# MY_DEMO_12864.net
KiCad netlist of a schematic drawn in Altium Designer
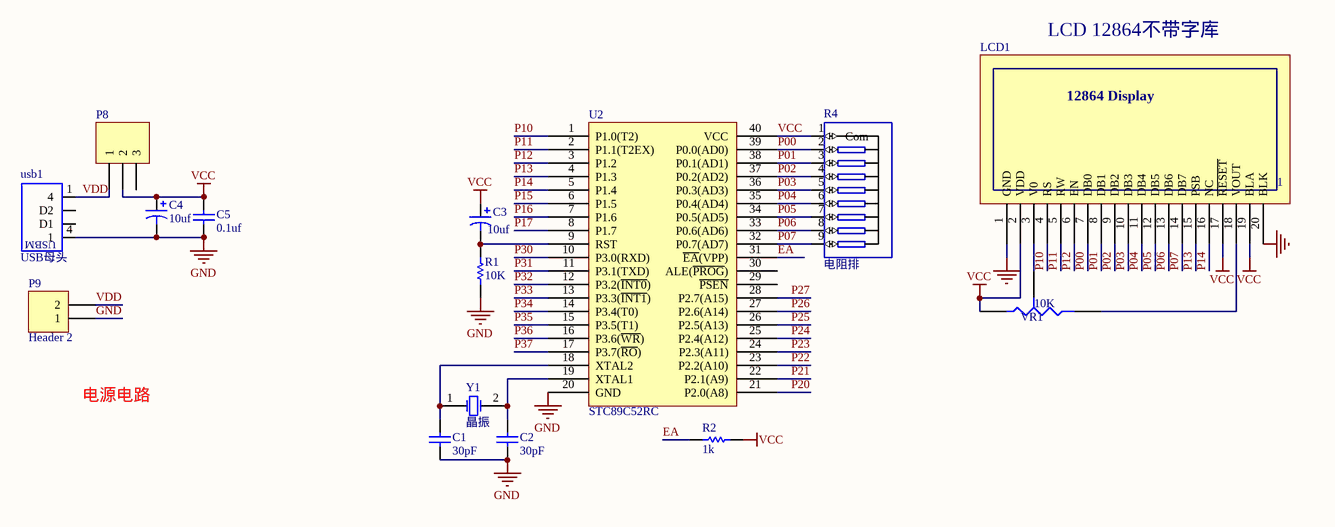
[diagram p0: MY_DEMO_12864.SchDoc]

(export (version "E")
  (design (tool "Eeschema 10.0.6"))
  (components
    (comp (ref "C1")
      (value "30pF")
      (footprint "RAD-0.1")
      (description "Capacitor")
      (fields (field (name "Comment") "瓷片电容") (field (name "PUBLISHER") "Altium Limited"))
      (libsource (lib "Miscellaneous Devices") (part "Cap"))
    )
    (comp (ref "C2")
      (value "30pF")
      (footprint "RAD-0.1")
      (description "Capacitor")
      (fields (field (name "Comment") "瓷片电容") (field (name "PUBLISHER") "Altium Limited"))
      (libsource (lib "Miscellaneous Devices") (part "Cap"))
    )
    (comp (ref "C3")
      (value "10uf")
      (footprint "10UF")
      (description "Polarized Capacitor (Radial)")
      (fields (field (name "Comment") "电解电容") (field (name "PUBLISHER") "Altium Limited"))
      (libsource (lib "Miscellaneous Devices") (part "Cap Pol1"))
    )
    (comp (ref "C4")
      (value "10uf")
      (footprint "10UF")
      (description "Polarized Capacitor (Radial)")
      (fields (field (name "Comment") "点解电容") (field (name "PUBLISHER") "Altium Limited"))
      (libsource (lib "Miscellaneous Devices") (part "Cap Pol1"))
    )
    (comp (ref "C5")
      (value "0.1uf")
      (footprint "CB1")
      (description "Capacitor")
      (fields (field (name "Comment") "瓷片电容") (field (name "PUBLISHER") "Altium Limited"))
      (libsource (lib "Miscellaneous Devices") (part "Cap"))
    )
    (comp (ref "LCD1") (value "1") (footprint "12864") (libsource (lib "*") (part "LCD12864-CK")))
    (comp (ref "P8")
      (value "Header 3")
      (footprint "HDR1X3")
      (description "Header, 3-Pin")
      (fields (field (name "PUBLISHER") "Altium Limited"))
      (libsource (lib "Miscellaneous Connectors") (part "Header 3"))
    )
    (comp (ref "P9")
      (value "Header 2")
      (footprint "HDR1X2")
      (description "Header, 2-Pin")
      (fields (field (name "PUBLISHER") "Altium Limited"))
      (libsource (lib "Miscellaneous Connectors") (part "Header 2"))
    )
    (comp (ref "R1")
      (value "10K")
      (footprint "电阻0.7-1.6")
      (description "Resistor")
      (fields (field (name "Comment") "电阻") (field (name "PUBLISHER") "Altium Limited"))
      (libsource (lib "Miscellaneous Devices") (part "Res1"))
    )
    (comp (ref "R2")
      (value "1k")
      (footprint "电阻0.7-1.6")
      (description "Resistor")
      (fields (field (name "Comment") "电阻") (field (name "PUBLISHER") "Altium Limited"))
      (libsource (lib "Miscellaneous Devices") (part "Res1"))
    )
    (comp (ref "R4") (value "电阻排") (footprint "插槽P9") (libsource (lib "电阻") (part "RES10")))
    (comp (ref "U2") (value "STC89C52RC") (footprint "DIP-40W") (libsource (lib "51单片机") (part "89C52")))
    (comp (ref "usb1") (value "USB母头") (footprint "A母USB") (libsource (lib "常用2") (part "USB")))
    (comp (ref "VR1")
      (value "12864")
      (footprint "RW")
      (fields (field (name "ALTIUM_UNNAMED_1") "10K"))
      (libsource (lib "*") (part "RES-TAP"))
    )
    (comp (ref "Y1")
      (value "晶振")
      (footprint "XTAL")
      (description "Crystal Oscillator")
      (fields (field (name "PUBLISHER") "Altium Limited"))
      (libsource (lib "Miscellaneous Devices") (part "XTAL"))
    )
  )
  (nets
    (net (code "1") (name "/EA") (class "Default")
      (node (ref "R2") (pin "2") (pinfunction "2_2") (pintype "passive"))
      (node (ref "U2") (pin "31") (pinfunction "~{EA}(VPP)_31") (pintype "passive"))
    )
    (net (code "3") (name "/P00") (class "Default")
      (node (ref "LCD1") (pin "7") (pinfunction "DB0_7") (pintype "passive"))
      (node (ref "R4") (pin "2") (pinfunction "2_2") (pintype "bidirectional"))
      (node (ref "U2") (pin "39") (pinfunction "P0.0(AD0)_39") (pintype "passive"))
    )
    (net (code "4") (name "/P01") (class "Default")
      (node (ref "LCD1") (pin "8") (pinfunction "DB1_8") (pintype "passive"))
      (node (ref "R4") (pin "3") (pinfunction "3_3") (pintype "bidirectional"))
      (node (ref "U2") (pin "38") (pinfunction "P0.1(AD1)_38") (pintype "passive"))
    )
    (net (code "5") (name "/P02") (class "Default")
      (node (ref "LCD1") (pin "9") (pinfunction "DB2_9") (pintype "passive"))
      (node (ref "R4") (pin "4") (pinfunction "4_4") (pintype "bidirectional"))
      (node (ref "U2") (pin "37") (pinfunction "P0.2(AD2)_37") (pintype "passive"))
    )
    (net (code "6") (name "/P03") (class "Default")
      (node (ref "LCD1") (pin "10") (pinfunction "DB3_10") (pintype "passive"))
      (node (ref "R4") (pin "5") (pinfunction "5_5") (pintype "bidirectional"))
      (node (ref "U2") (pin "36") (pinfunction "P0.3(AD3)_36") (pintype "passive"))
    )
    (net (code "7") (name "/P04") (class "Default")
      (node (ref "LCD1") (pin "11") (pinfunction "DB4_11") (pintype "passive"))
      (node (ref "R4") (pin "6") (pinfunction "6_6") (pintype "bidirectional"))
      (node (ref "U2") (pin "35") (pinfunction "P0.4(AD4)_35") (pintype "passive"))
    )
    (net (code "8") (name "/P05") (class "Default")
      (node (ref "LCD1") (pin "12") (pinfunction "DB5_12") (pintype "passive"))
      (node (ref "R4") (pin "7") (pinfunction "7_7") (pintype "bidirectional"))
      (node (ref "U2") (pin "34") (pinfunction "P0.5(AD5)_34") (pintype "passive"))
    )
    (net (code "9") (name "/P06") (class "Default")
      (node (ref "LCD1") (pin "13") (pinfunction "DB6_13") (pintype "passive"))
      (node (ref "R4") (pin "8") (pinfunction "8_8") (pintype "bidirectional"))
      (node (ref "U2") (pin "33") (pinfunction "P0.6(AD6)_33") (pintype "passive"))
    )
    (net (code "10") (name "/P07") (class "Default")
      (node (ref "LCD1") (pin "14") (pinfunction "DB7_14") (pintype "passive"))
      (node (ref "R4") (pin "9") (pinfunction "9_9") (pintype "bidirectional"))
      (node (ref "U2") (pin "32") (pinfunction "P0.7(AD7)_32") (pintype "passive"))
    )
    (net (code "11") (name "/P10") (class "Default")
      (node (ref "LCD1") (pin "4") (pinfunction "RS_4") (pintype "passive"))
      (node (ref "U2") (pin "1") (pinfunction "P1.0(T2)_1") (pintype "passive"))
    )
    (net (code "12") (name "/P11") (class "Default")
      (node (ref "LCD1") (pin "5") (pinfunction "RW_5") (pintype "passive"))
      (node (ref "U2") (pin "2") (pinfunction "P1.1(T2EX)_2") (pintype "passive"))
    )
    (net (code "13") (name "/P12") (class "Default")
      (node (ref "LCD1") (pin "6") (pinfunction "EN_6") (pintype "passive"))
      (node (ref "U2") (pin "3") (pinfunction "P1.2_3") (pintype "passive"))
    )
    (net (code "14") (name "/P13") (class "Default")
      (node (ref "LCD1") (pin "15") (pinfunction "PSB_15") (pintype "passive"))
      (node (ref "U2") (pin "4") (pinfunction "P1.3_4") (pintype "passive"))
    )
    (net (code "15") (name "/P14") (class "Default")
      (node (ref "LCD1") (pin "16") (pinfunction "NC_16") (pintype "passive"))
      (node (ref "U2") (pin "5") (pinfunction "P1.4_5") (pintype "passive"))
    )
    (net (code "16") (name "/P15") (class "Default")
      (node (ref "U2") (pin "6") (pinfunction "P1.5_6") (pintype "passive"))
    )
    (net (code "17") (name "/P16") (class "Default")
      (node (ref "U2") (pin "7") (pinfunction "P1.6_7") (pintype "passive"))
    )
    (net (code "18") (name "/P17") (class "Default")
      (node (ref "U2") (pin "8") (pinfunction "P1.7_8") (pintype "passive"))
    )
    (net (code "19") (name "/P20") (class "Default")
      (node (ref "U2") (pin "21") (pinfunction "P2.0(A8)_21") (pintype "passive"))
    )
    (net (code "20") (name "/P21") (class "Default")
      (node (ref "U2") (pin "22") (pinfunction "P2.1(A9)_22") (pintype "passive"))
    )
    (net (code "21") (name "/P22") (class "Default")
      (node (ref "U2") (pin "23") (pinfunction "P2.2(A10)_23") (pintype "passive"))
    )
    (net (code "22") (name "/P23") (class "Default")
      (node (ref "U2") (pin "24") (pinfunction "P2.3(A11)_24") (pintype "passive"))
    )
    (net (code "23") (name "/P24") (class "Default")
      (node (ref "U2") (pin "25") (pinfunction "P2.4(A12)_25") (pintype "passive"))
    )
    (net (code "24") (name "/P25") (class "Default")
      (node (ref "U2") (pin "26") (pinfunction "P2.5(A13)_26") (pintype "passive"))
    )
    (net (code "25") (name "/P26") (class "Default")
      (node (ref "U2") (pin "27") (pinfunction "P2.6(A14)_27") (pintype "passive"))
    )
    (net (code "26") (name "/P27") (class "Default")
      (node (ref "U2") (pin "28") (pinfunction "P2.7(A15)_28") (pintype "passive"))
    )
    (net (code "27") (name "/P30") (class "Default")
      (node (ref "U2") (pin "10") (pinfunction "P3.0(RXD)_10") (pintype "passive"))
    )
    (net (code "28") (name "/P31") (class "Default")
      (node (ref "U2") (pin "11") (pinfunction "P3.1(TXD)_11") (pintype "passive"))
    )
    (net (code "29") (name "/P32") (class "Default")
      (node (ref "U2") (pin "12") (pinfunction "P3.2(~{INT0})_12") (pintype "passive"))
    )
    (net (code "30") (name "/P33") (class "Default")
      (node (ref "U2") (pin "13") (pinfunction "P3.3(~{INT1})_13") (pintype "passive"))
    )
    (net (code "31") (name "/P34") (class "Default")
      (node (ref "U2") (pin "14") (pinfunction "P3.4(T0)_14") (pintype "passive"))
    )
    (net (code "32") (name "/P35") (class "Default")
      (node (ref "U2") (pin "15") (pinfunction "P3.5(T1)_15") (pintype "passive"))
    )
    (net (code "33") (name "/P36") (class "Default")
      (node (ref "U2") (pin "16") (pinfunction "P3.6(~{WR})_16") (pintype "passive"))
    )
    (net (code "34") (name "/P37") (class "Default")
      (node (ref "U2") (pin "17") (pinfunction "P3.7(~{RO})_17") (pintype "passive"))
    )
    (net (code "35") (name "/VDD") (class "Default")
      (node (ref "P8") (pin "1") (pinfunction "1_1") (pintype "passive"))
      (node (ref "P9") (pin "2") (pinfunction "2_2") (pintype "passive"))
      (node (ref "usb1") (pin "1") (pinfunction "4_1") (pintype "passive"))
    )
    (net (code "36") (name "GND") (class "Default")
      (node (ref "C1") (pin "1") (pinfunction "1_1") (pintype "passive"))
      (node (ref "C2") (pin "1") (pinfunction "1_1") (pintype "passive"))
      (node (ref "C4") (pin "2") (pinfunction "2_2") (pintype "passive"))
      (node (ref "C5") (pin "1") (pinfunction "1_1") (pintype "passive"))
      (node (ref "LCD1") (pin "1") (pinfunction "GND_1") (pintype "passive"))
      (node (ref "LCD1") (pin "20") (pinfunction "BLK_20") (pintype "passive"))
      (node (ref "P9") (pin "1") (pinfunction "1_1") (pintype "passive"))
      (node (ref "R1") (pin "1") (pinfunction "1_1") (pintype "passive"))
      (node (ref "U2") (pin "20") (pinfunction "GND_20") (pintype "passive"))
      (node (ref "usb1") (pin "4") (pinfunction "1_4") (pintype "passive"))
    )
    (net (code "37") (name "Net-(LCD1-V0)") (class "Default")
      (node (ref "LCD1") (pin "3") (pinfunction "V0_3") (pintype "passive"))
      (node (ref "VR1") (pin "2") (pinfunction "2_2") (pintype "passive"))
    )
    (net (code "38") (name "Net-(LCD1-VOUT)") (class "Default")
      (node (ref "LCD1") (pin "18") (pinfunction "VOUT_18") (pintype "passive"))
      (node (ref "VR1") (pin "3") (pinfunction "3_3") (pintype "passive"))
    )
    (net (code "39") (name "Net-(U2-RST)") (class "Default")
      (node (ref "C3") (pin "2") (pinfunction "2_2") (pintype "passive"))
      (node (ref "R1") (pin "2") (pinfunction "2_2") (pintype "passive"))
      (node (ref "U2") (pin "9") (pinfunction "RST_9") (pintype "passive"))
    )
    (net (code "40") (name "Net-(U2-XTAL1)") (class "Default")
      (node (ref "C2") (pin "2") (pinfunction "2_2") (pintype "passive"))
      (node (ref "U2") (pin "19") (pinfunction "XTAL1_19") (pintype "passive"))
      (node (ref "Y1") (pin "2") (pinfunction "OSC2_2") (pintype "passive"))
    )
    (net (code "41") (name "Net-(U2-XTAL2)") (class "Default")
      (node (ref "C1") (pin "2") (pinfunction "2_2") (pintype "passive"))
      (node (ref "U2") (pin "18") (pinfunction "XTAL2_18") (pintype "passive"))
      (node (ref "Y1") (pin "1") (pinfunction "OSC1_1") (pintype "passive"))
    )
    (net (code "42") (name "VCC") (class "Default")
      (node (ref "C3") (pin "1") (pinfunction "1_1") (pintype "passive"))
      (node (ref "C4") (pin "1") (pinfunction "1_1") (pintype "passive"))
      (node (ref "C5") (pin "2") (pinfunction "2_2") (pintype "passive"))
      (node (ref "LCD1") (pin "17") (pinfunction "~{RESET}_17") (pintype "passive"))
      (node (ref "LCD1") (pin "19") (pinfunction "BLA_19") (pintype "passive"))
      (node (ref "LCD1") (pin "2") (pinfunction "VDD_2") (pintype "passive"))
      (node (ref "P8") (pin "2") (pinfunction "2_2") (pintype "passive"))
      (node (ref "R2") (pin "1") (pinfunction "1_1") (pintype "passive"))
      (node (ref "R4") (pin "1") (pinfunction "Com_1") (pintype "bidirectional"))
      (node (ref "U2") (pin "40") (pinfunction "VCC_40") (pintype "passive"))
      (node (ref "VR1") (pin "1") (pinfunction "1_1") (pintype "passive"))
    )
    (net (code "43") (name "unconnected-(P8-Pad3)") (class "Default")
      (node (ref "P8") (pin "3") (pinfunction "3_3") (pintype "passive"))
    )
    (net (code "44") (name "unconnected-(U2-ALE(~{PROG})-Pad30)") (class "Default")
      (node (ref "U2") (pin "30") (pinfunction "ALE(~{PROG})_30") (pintype "passive"))
    )
    (net (code "45") (name "unconnected-(U2-~{PSEN}-Pad29)") (class "Default")
      (node (ref "U2") (pin "29") (pinfunction "~{PSEN}_29") (pintype "passive"))
    )
    (net (code "46") (name "unconnected-(usb1-PadD1)") (class "Default")
      (node (ref "usb1") (pin "D1") (pinfunction "D1_D1") (pintype "passive"))
    )
    (net (code "47") (name "unconnected-(usb1-PadD2)") (class "Default")
      (node (ref "usb1") (pin "D2") (pinfunction "D2_D2") (pintype "passive"))
    )
  )
)
